# REG3V3.net
KiCad netlist of a schematic drawn in Altium Designer
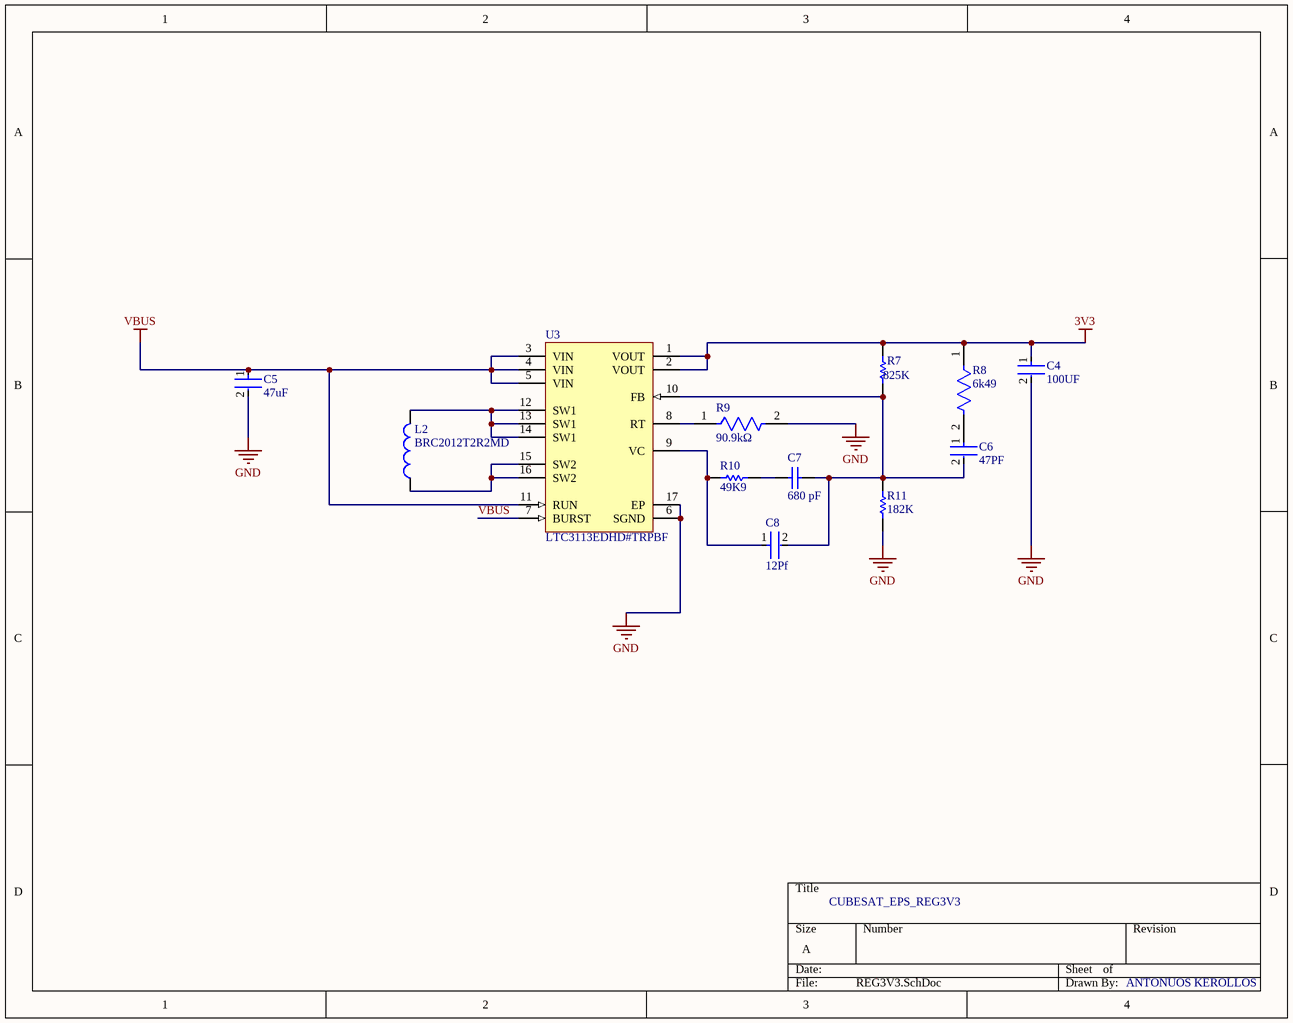
[diagram p0: REG3V3.SchDoc]

(export (version "E")
  (design (tool "Eeschema 10.0.6"))
  (components
    (comp (ref "C4")
      (value "100UF")
      (footprint "FP-C1210C-FS-MFG")
      (description "CAP CER 100UF 16V X5R 1210")
      (fields (field (name "TOLERANCE") "20%"))
      (libsource (lib "Altium Content Vault") (part "02cd4be3c70576c341d710602a673aa"))
    )
    (comp (ref "C5")
      (value "47uF")
      (footprint "FP-C3216-160-0_2-MFG")
      (description "Multilayer Ceramic Capacitors 47uF ±20% 25V X5R SMD 1206")
      (fields (field (name "VOLTAGE") "25V") (field (name "TOLERANCE") "20%"))
      (libsource (lib "Altium Content Vault") (part "11868f565c42a9108669ba33697ecf6"))
    )
    (comp (ref "C6")
      (value "47PF")
      (footprint "FP-C0805C-DN-MFG")
      (description "CAP CER 47PF 50V C0G/NP0 0805")
      (fields
        (field (name "MANUFACTURER") "KEMET")
        (field (name "MANUFACTURER PART NUMBER") "C0805C470J5GACTU")
      )
      (libsource (lib "Altium Content Vault") (part "b4654b650e69147ec39a6b967a45e02"))
    )
    (comp (ref "C7")
      (value "680 pF")
      (footprint "CAPC1005X55X25ML05T10")
      (description "Chip Capacitor, 680 pF, +/- 10%, 50 V, -55 to 125 degC, 0402 (1005 Metric), RoHS, Tape and Reel")
      (fields (field (name "TOLERANCE") "10%") (field (name "MANUFACTURER") "Basic Passives"))
      (libsource (lib "Altium Content Vault") (part "CAP-NP-2"))
    )
    (comp (ref "C8")
      (value "12Pf")
      (footprint "FP-C0603C-CF-MFG")
      (description "Ceramic Capacitor 12Pf 50V, C0G, 5%, 0603, Full Reel")
      (fields (field (name "MANUFACTURER") "KEMET") (field (name "TOLERANCE") "0.05"))
      (libsource (lib "Altium Content Vault") (part "b4654b650e69147ec39a6b967a45e02"))
    )
    (comp (ref "L2")
      (value "BRC2012T2R2MD")
      (footprint "INDC2013X140X50LL20T20")
      (fields (field (name "TOLERANCE") "±20%") (field (name "MANUFACTURER") "Taiyo Yuden"))
      (libsource (lib "Altium Content Vault") (part "IND-2"))
    )
    (comp (ref "R7")
      (value "825K")
      (footprint "RESC1005X40X25NL05T05")
      (fields (field (name "MANUFACTURER") "Vishay Dale") (field (name "PART NUMBER") "CRCW0402825KFKED"))
      (libsource (lib "Altium Content Vault") (part "RES"))
    )
    (comp (ref "R8")
      (value "6k49")
      (footprint "FP-ERJ2RK-MFG")
      (fields (field (name "TOLERANCE") "1%"))
      (libsource (lib "Altium Content Vault") (part "1029c3af85768c4190bb7ad29bc67b5"))
    )
    (comp (ref "R9")
      (value "90.9kΩ")
      (footprint "FP-CRCW0402-e3-IPC_B")
      (description "RES Thick Film, 90.9kΩ, 1%, 0.063W, 100ppm/°C, 0402")
      (fields (field (name "TOLERANCE") "1%"))
      (libsource (lib "Altium Content Vault") (part "1029c3af85768c4190bb7ad29bc67b5"))
    )
    (comp (ref "R10")
      (value "49K9")
      (footprint "RESC1005X40X25LL05T05")
      (fields (field (name "PART NUMBER") "CRCW040249K9FKED") (field (name "MANUFACTURER") "Vishay Dale"))
      (libsource (lib "Altium Content Vault") (part "RES"))
    )
    (comp (ref "R11")
      (value "182K")
      (footprint "RESC1005X40X25ML05T05")
      (fields (field (name "MANUFACTURER") "Vishay Dale") (field (name "PART NUMBER") "CRCW0402182KFKED"))
      (libsource (lib "Altium Content Vault") (part "RES"))
    )
    (comp (ref "U3")
      (value "LTC3113EDHD#TRPBF")
      (footprint "LT-DHD-16_V")
      (fields (field (name "MANUFACTURER") "Linear Technology"))
      (libsource (lib "Altium Content Vault") (part "LT-LTC3113-DHD-16"))
    )
  )
  (nets
    (net (code "1") (name "3V3") (class "Default")
      (node (ref "C4") (pin "1") (pinfunction "1_1") (pintype "passive"))
      (node (ref "R7") (pin "2") (pinfunction "2_2") (pintype "passive"))
      (node (ref "R8") (pin "1") (pinfunction "1_1") (pintype "passive"))
      (node (ref "U3") (pin "1") (pinfunction "VOUT_1") (pintype "power_in"))
      (node (ref "U3") (pin "2") (pinfunction "VOUT_2") (pintype "power_in"))
    )
    (net (code "2") (name "GND") (class "Default")
      (node (ref "C4") (pin "2") (pinfunction "2_2") (pintype "passive"))
      (node (ref "C5") (pin "2") (pinfunction "2_2") (pintype "passive"))
      (node (ref "R11") (pin "2") (pinfunction "2_2") (pintype "passive"))
      (node (ref "R9") (pin "2") (pinfunction "2_2") (pintype "passive"))
      (node (ref "U3") (pin "17") (pinfunction "EP_17") (pintype "power_in"))
      (node (ref "U3") (pin "6") (pinfunction "SGND_6") (pintype "power_in"))
    )
    (net (code "3") (name "Net-(C6-Pad1)") (class "Default")
      (node (ref "C6") (pin "1") (pinfunction "1_1") (pintype "passive"))
      (node (ref "R8") (pin "2") (pinfunction "2_2") (pintype "passive"))
    )
    (net (code "4") (name "Net-(C7-Pad1)") (class "Default")
      (node (ref "C7") (pin "1") (pinfunction "1_1") (pintype "passive"))
      (node (ref "R10") (pin "2") (pinfunction "2_2") (pintype "passive"))
    )
    (net (code "5") (name "Net-(L2-Pad1)") (class "Default")
      (node (ref "L2") (pin "1") (pinfunction "1_1") (pintype "passive"))
      (node (ref "U3") (pin "15") (pinfunction "SW2_15") (pintype "passive"))
      (node (ref "U3") (pin "16") (pinfunction "SW2_16") (pintype "passive"))
    )
    (net (code "6") (name "Net-(L2-Pad2)") (class "Default")
      (node (ref "L2") (pin "2") (pinfunction "2_2") (pintype "passive"))
      (node (ref "U3") (pin "12") (pinfunction "SW1_12") (pintype "passive"))
      (node (ref "U3") (pin "13") (pinfunction "SW1_13") (pintype "passive"))
      (node (ref "U3") (pin "14") (pinfunction "SW1_14") (pintype "passive"))
    )
    (net (code "7") (name "Net-(U3-FB)") (class "Default")
      (node (ref "C6") (pin "2") (pinfunction "2_2") (pintype "passive"))
      (node (ref "C7") (pin "2") (pinfunction "2_2") (pintype "passive"))
      (node (ref "C8") (pin "2") (pinfunction "2_2") (pintype "passive"))
      (node (ref "R11") (pin "1") (pinfunction "1_1") (pintype "passive"))
      (node (ref "R7") (pin "1") (pinfunction "1_1") (pintype "passive"))
      (node (ref "U3") (pin "10") (pinfunction "FB_10") (pintype "input"))
    )
    (net (code "8") (name "Net-(U3-RT)") (class "Default")
      (node (ref "R9") (pin "1") (pinfunction "1_1") (pintype "passive"))
      (node (ref "U3") (pin "8") (pinfunction "RT_8") (pintype "passive"))
    )
    (net (code "9") (name "Net-(U3-VC)") (class "Default")
      (node (ref "C8") (pin "1") (pinfunction "1_1") (pintype "passive"))
      (node (ref "R10") (pin "1") (pinfunction "1_1") (pintype "passive"))
      (node (ref "U3") (pin "9") (pinfunction "VC_9") (pintype "passive"))
    )
    (net (code "10") (name "VBUS") (class "Default")
      (node (ref "C5") (pin "1") (pinfunction "1_1") (pintype "passive"))
      (node (ref "U3") (pin "11") (pinfunction "RUN_11") (pintype "input"))
      (node (ref "U3") (pin "3") (pinfunction "VIN_3") (pintype "power_in"))
      (node (ref "U3") (pin "4") (pinfunction "VIN_4") (pintype "power_in"))
      (node (ref "U3") (pin "5") (pinfunction "VIN_5") (pintype "power_in"))
      (node (ref "U3") (pin "7") (pinfunction "BURST_7") (pintype "input"))
    )
  )
)
